# Prototipo_1_0.net
KiCad netlist of a schematic drawn in EAGLE
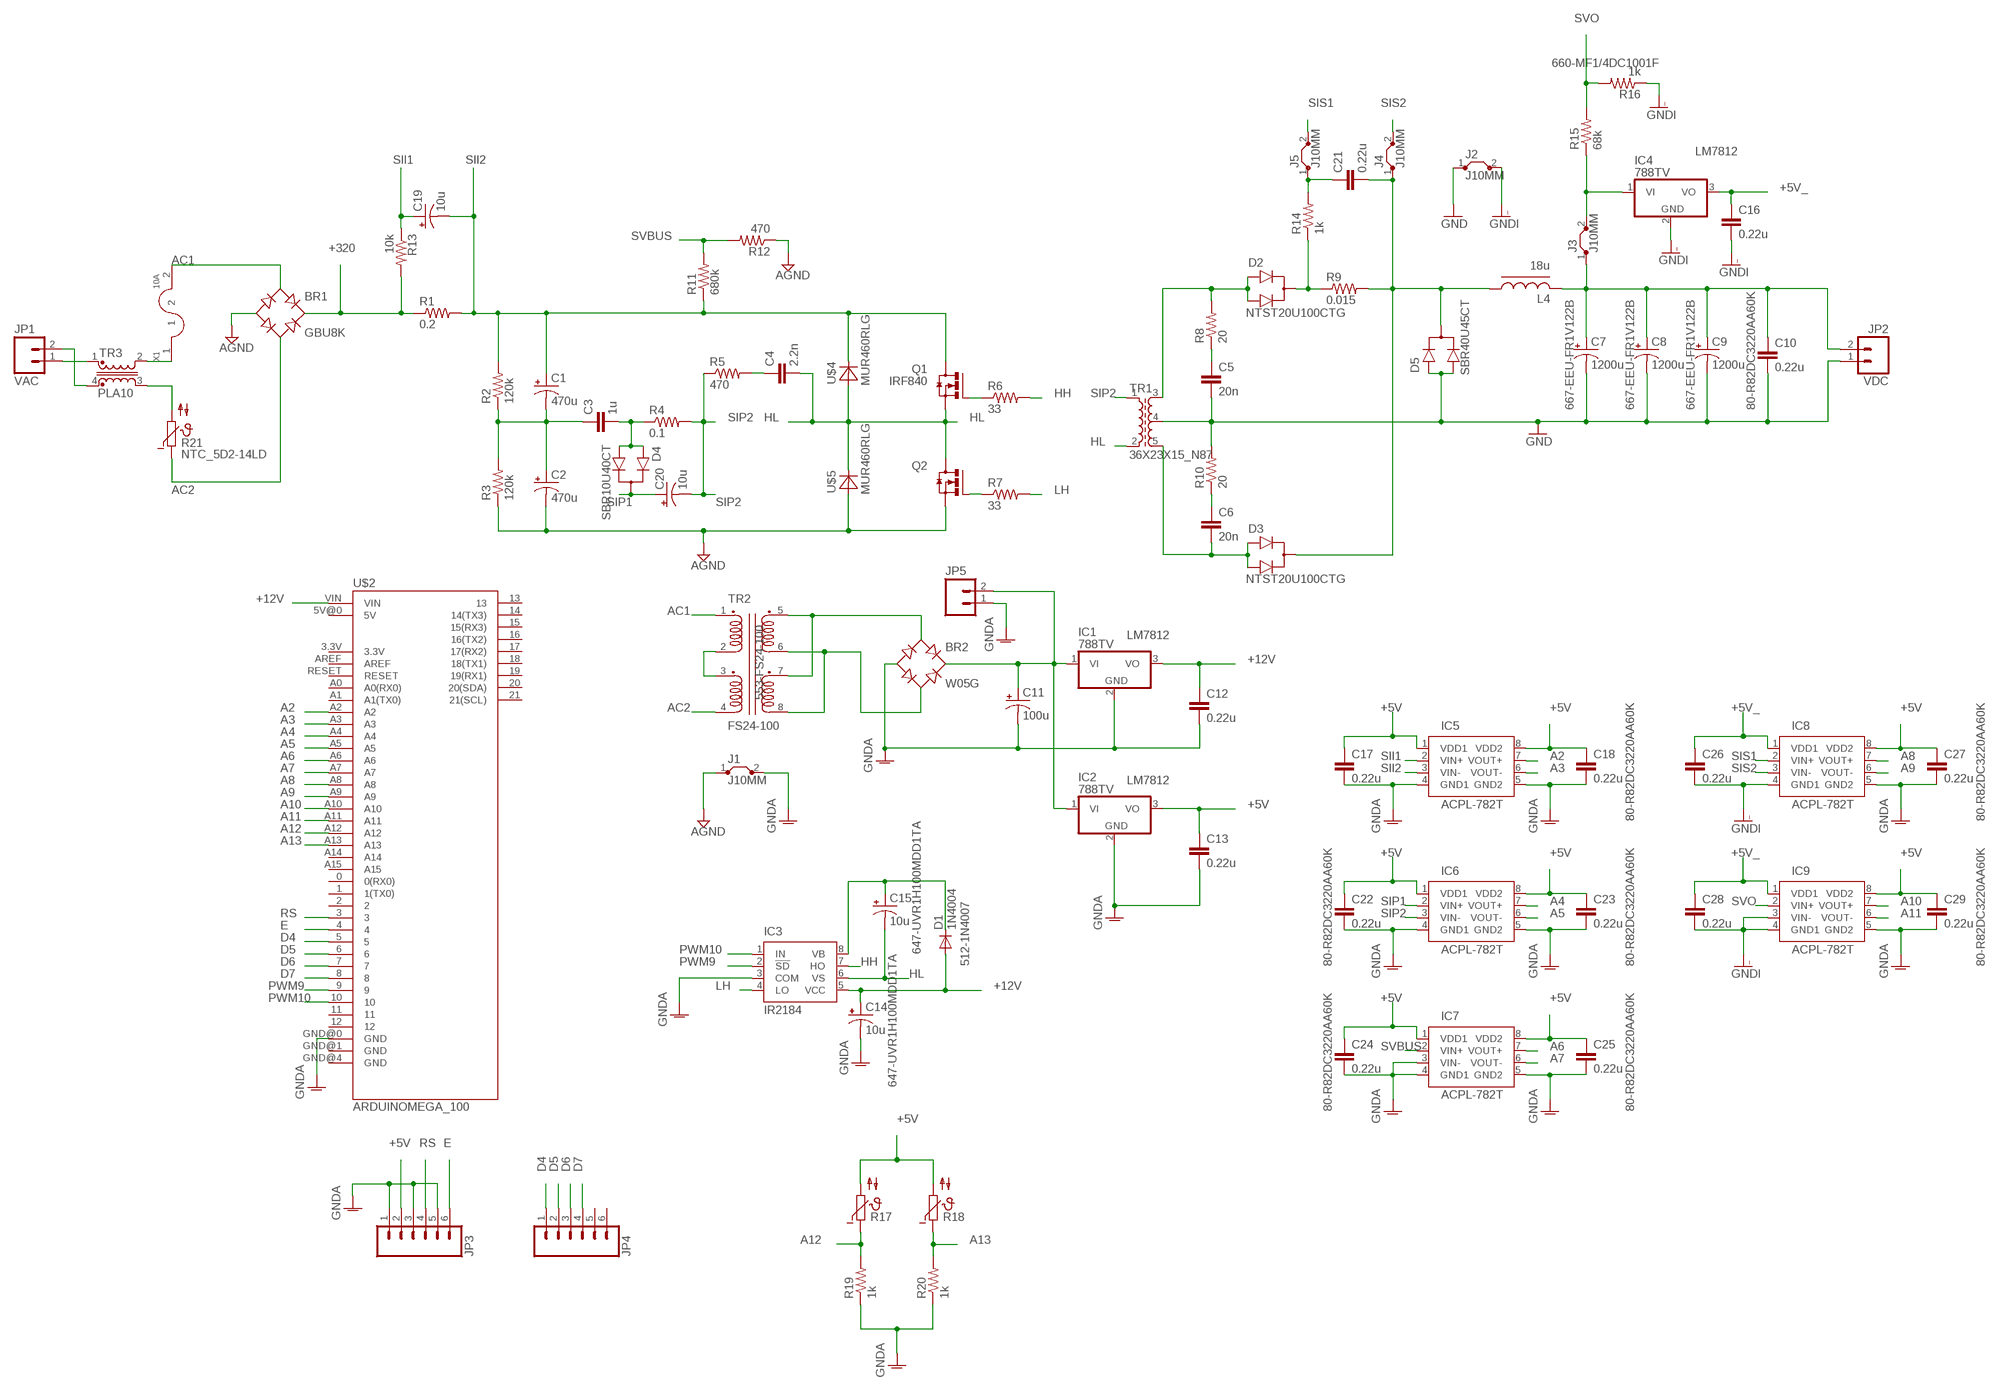
[diagram p0: schematic, sheet 1]

(export (version "E")
  (design (tool "Eeschema 10.0.6"))
  (components
    (comp (ref "BR1")
      (value "GBU8K")
      (footprint "eagle-import:GBU")
      (libsource (lib "eagle-import") (part "GBU8K"))
    )
    (comp (ref "BR2")
      (value "W05G")
      (footprint "eagle-import:WOG")
      (libsource (lib "eagle-import") (part "WG05"))
    )
    (comp (ref "C1")
      (value "470u")
      (footprint "eagle-import:CPOL_RADIAL_470UF_250V")
      (libsource (lib "eagle-import") (part "CAP_470UF_250V"))
    )
    (comp (ref "C2")
      (value "470u")
      (footprint "eagle-import:CPOL_RADIAL_470UF_250V")
      (libsource (lib "eagle-import") (part "CAP_470UF_250V"))
    )
    (comp (ref "C3")
      (value "1u")
      (footprint "eagle-import:C22.5B8")
      (libsource (lib "eagle-import") (part "C22/8"))
    )
    (comp (ref "C4")
      (value "2.2n")
      (footprint "eagle-import:C7.5B4")
      (libsource (lib "eagle-import") (part "C7.5/4"))
    )
    (comp (ref "C5")
      (value "20n")
      (footprint "eagle-import:C10B4")
      (libsource (lib "eagle-import") (part "C10/4"))
    )
    (comp (ref "C6")
      (value "20n")
      (footprint "eagle-import:C10B4")
      (libsource (lib "eagle-import") (part "C10/4"))
    )
    (comp (ref "C7")
      (value "1200u")
      (footprint "eagle-import:CPOL-RADIAL-1000UF-25V")
      (fields (field (name "MOUSER") "667-EEU-FR1V122B"))
      (libsource (lib "eagle-import") (part "CAP_POLPTH4"))
    )
    (comp (ref "C8")
      (value "1200u")
      (footprint "eagle-import:CPOL-RADIAL-1000UF-25V")
      (fields (field (name "MOUSER") "667-EEU-FR1V122B"))
      (libsource (lib "eagle-import") (part "CAP_POLPTH4"))
    )
    (comp (ref "C9")
      (value "1200u")
      (footprint "eagle-import:CPOL-RADIAL-1000UF-25V")
      (fields (field (name "MOUSER") "667-EEU-FR1V122B"))
      (libsource (lib "eagle-import") (part "CAP_POLPTH4"))
    )
    (comp (ref "C10")
      (value "0.22u")
      (footprint "eagle-import:C5B3")
      (fields (field (name "MOUSER") "80-R82DC3220AA60K "))
      (libsource (lib "eagle-import") (part "C5/3"))
    )
    (comp (ref "C11")
      (value "100u")
      (footprint "eagle-import:E3,5-8")
      (libsource (lib "eagle-import") (part "CPOL-USE3.5-8"))
    )
    (comp (ref "C12")
      (value "0.22u")
      (footprint "eagle-import:C5B3")
      (libsource (lib "eagle-import") (part "C5/3"))
    )
    (comp (ref "C13")
      (value "0.22u")
      (footprint "eagle-import:C5B3")
      (libsource (lib "eagle-import") (part "C5/3"))
    )
    (comp (ref "C14")
      (value "10u")
      (footprint "eagle-import:E2,5-6E")
      (fields (field (name "MOUSER") "647-UVR1H100MDD1TA"))
      (libsource (lib "eagle-import") (part "CPOL-USE2,5-6E"))
    )
    (comp (ref "C15")
      (value "10u")
      (footprint "eagle-import:E2,5-6E")
      (fields (field (name "MOUSER") "647-UVR1H100MDD1TA"))
      (libsource (lib "eagle-import") (part "CPOL-USE2,5-6E"))
    )
    (comp (ref "C16")
      (value "0.22u")
      (footprint "eagle-import:C5B3")
      (libsource (lib "eagle-import") (part "C5/3"))
    )
    (comp (ref "C17")
      (value "0.22u")
      (footprint "eagle-import:C5B3")
      (libsource (lib "eagle-import") (part "C5/3"))
    )
    (comp (ref "C18")
      (value "0.22u")
      (footprint "eagle-import:C5B3")
      (fields (field (name "MOUSER") "80-R82DC3220AA60K "))
      (libsource (lib "eagle-import") (part "C5/3"))
    )
    (comp (ref "C19")
      (value "10u")
      (footprint "eagle-import:E2,5-6E")
      (libsource (lib "eagle-import") (part "CPOL-USE2,5-6E"))
    )
    (comp (ref "C20")
      (value "10u")
      (footprint "eagle-import:E2,5-6E")
      (libsource (lib "eagle-import") (part "CPOL-USE2,5-6E"))
    )
    (comp (ref "C21")
      (value "0.22u")
      (footprint "eagle-import:C5B3")
      (libsource (lib "eagle-import") (part "C5/3"))
    )
    (comp (ref "C22")
      (value "0.22u")
      (footprint "eagle-import:C5B3")
      (fields (field (name "MOUSER") "80-R82DC3220AA60K "))
      (libsource (lib "eagle-import") (part "C5/3"))
    )
    (comp (ref "C23")
      (value "0.22u")
      (footprint "eagle-import:C5B3")
      (fields (field (name "MOUSER") "80-R82DC3220AA60K "))
      (libsource (lib "eagle-import") (part "C5/3"))
    )
    (comp (ref "C24")
      (value "0.22u")
      (footprint "eagle-import:C5B3")
      (fields (field (name "MOUSER") "80-R82DC3220AA60K "))
      (libsource (lib "eagle-import") (part "C5/3"))
    )
    (comp (ref "C25")
      (value "0.22u")
      (footprint "eagle-import:C5B3")
      (fields (field (name "MOUSER") "80-R82DC3220AA60K "))
      (libsource (lib "eagle-import") (part "C5/3"))
    )
    (comp (ref "C26")
      (value "0.22u")
      (footprint "eagle-import:C5B3")
      (libsource (lib "eagle-import") (part "C5/3"))
    )
    (comp (ref "C27")
      (value "0.22u")
      (footprint "eagle-import:C5B3")
      (fields (field (name "MOUSER") "80-R82DC3220AA60K "))
      (libsource (lib "eagle-import") (part "C5/3"))
    )
    (comp (ref "C28")
      (value "0.22u")
      (footprint "eagle-import:C5B3")
      (libsource (lib "eagle-import") (part "C5/3"))
    )
    (comp (ref "C29")
      (value "0.22u")
      (footprint "eagle-import:C5B3")
      (fields (field (name "MOUSER") "80-R82DC3220AA60K "))
      (libsource (lib "eagle-import") (part "C5/3"))
    )
    (comp (ref "D1")
      (value "1N4004")
      (footprint "eagle-import:DO41-10")
      (fields (field (name "MOUSER") "512-1N4007"))
      (libsource (lib "eagle-import") (part "1N4004"))
    )
    (comp (ref "D2")
      (value "NTST20U100CTG")
      (footprint "eagle-import:TO220V")
      (libsource (lib "eagle-import") (part "NTST20U100CTG"))
    )
    (comp (ref "D3")
      (value "NTST20U100CTG")
      (footprint "eagle-import:TO220V")
      (libsource (lib "eagle-import") (part "NTST20U100CTG"))
    )
    (comp (ref "D4")
      (value "SBR10U40CT")
      (footprint "eagle-import:TO220V")
      (libsource (lib "eagle-import") (part "SBR10U40CT"))
    )
    (comp (ref "D5")
      (value "SBR40U45CT")
      (footprint "eagle-import:TO220V")
      (libsource (lib "eagle-import") (part "SBR40U45CT"))
    )
    (comp (ref "IC1")
      (value "788TV")
      (footprint "eagle-import:TO220V")
      (fields (field (name "MODEL") "LM7812"))
      (libsource (lib "eagle-import") (part "78TV8"))
    )
    (comp (ref "IC2")
      (value "788TV")
      (footprint "eagle-import:TO220V")
      (fields (field (name "MODEL") "LM7812"))
      (libsource (lib "eagle-import") (part "78TV8"))
    )
    (comp (ref "IC3")
      (value "IR2184")
      (footprint "eagle-import:DIL08")
      (fields (field (name "MF") "INTERNATIONAL RECTIFIER(IR)"))
      (libsource (lib "eagle-import") (part "IR2184"))
    )
    (comp (ref "IC4")
      (value "788TV")
      (footprint "eagle-import:TO220V")
      (fields (field (name "MODEL") "LM7812"))
      (libsource (lib "eagle-import") (part "78TV8"))
    )
    (comp (ref "IC5")
      (value "ACPL-782T")
      (footprint "eagle-import:DIL08")
      (libsource (lib "eagle-import") (part "ACPL-782T"))
    )
    (comp (ref "IC6")
      (value "ACPL-782T")
      (footprint "eagle-import:DIL08")
      (libsource (lib "eagle-import") (part "ACPL-782T"))
    )
    (comp (ref "IC7")
      (value "ACPL-782T")
      (footprint "eagle-import:DIL08")
      (libsource (lib "eagle-import") (part "ACPL-782T"))
    )
    (comp (ref "IC8")
      (value "ACPL-782T")
      (footprint "eagle-import:DIL08")
      (libsource (lib "eagle-import") (part "ACPL-782T"))
    )
    (comp (ref "IC9")
      (value "ACPL-782T")
      (footprint "eagle-import:DIL08")
      (libsource (lib "eagle-import") (part "ACPL-782T"))
    )
    (comp (ref "J1")
      (value "J10MM")
      (footprint "eagle-import:10")
      (libsource (lib "eagle-import") (part "J10MM"))
    )
    (comp (ref "J2")
      (value "J10MM")
      (footprint "eagle-import:10")
      (libsource (lib "eagle-import") (part "J10MM"))
    )
    (comp (ref "J3")
      (value "J10MM")
      (footprint "eagle-import:10")
      (libsource (lib "eagle-import") (part "J10MM"))
    )
    (comp (ref "J4")
      (value "J10MM")
      (footprint "eagle-import:10")
      (libsource (lib "eagle-import") (part "J10MM"))
    )
    (comp (ref "J5")
      (value "J10MM")
      (footprint "eagle-import:10")
      (libsource (lib "eagle-import") (part "J10MM"))
    )
    (comp (ref "JP1")
      (value "VAC")
      (footprint "eagle-import:SCREWTERMINAL-3.5MM-2")
      (libsource (lib "eagle-import") (part "M023.5MM"))
    )
    (comp (ref "JP2")
      (value "VDC")
      (footprint "eagle-import:SCREWTERMINAL-5MM-2")
      (libsource (lib "eagle-import") (part "M025MM"))
    )
    (comp (ref "JP3")
      (value "M06SIP")
      (footprint "eagle-import:1X06")
      (libsource (lib "eagle-import") (part "M06SIP"))
    )
    (comp (ref "JP4")
      (value "M06SIP")
      (footprint "eagle-import:1X06")
      (libsource (lib "eagle-import") (part "M06SIP"))
    )
    (comp (ref "JP5")
      (value "M02LOCK_LONGPADS")
      (footprint "eagle-import:1X02_LOCK_LONGPADS")
      (libsource (lib "eagle-import") (part "M02LOCK_LONGPADS"))
    )
    (comp (ref "L4")
      (value "18u")
      (footprint "eagle-import:CHOKE_18U")
      (libsource (lib "eagle-import") (part "CHOKE_18U"))
    )
    (comp (ref "Q1")
      (value "IRF840")
      (footprint "eagle-import:TO220HV")
      (libsource (lib "eagle-import") (part "IRF840"))
    )
    (comp (ref "Q2")
      (value "IRF840")
      (footprint "eagle-import:TO220HV")
      (libsource (lib "eagle-import") (part "IRF840"))
    )
    (comp (ref "R1")
      (value "0.2")
      (footprint "eagle-import:AXIAL-0.6")
      (libsource (lib "eagle-import") (part "RESISTORPTH-1W"))
    )
    (comp (ref "R2")
      (value "120k")
      (footprint "eagle-import:AXIAL-0.4")
      (libsource (lib "eagle-import") (part "RESISTORPTH-1/4W"))
    )
    (comp (ref "R3")
      (value "120k")
      (footprint "eagle-import:AXIAL-0.4")
      (libsource (lib "eagle-import") (part "RESISTORPTH-1/4W"))
    )
    (comp (ref "R4")
      (value "0.1")
      (footprint "eagle-import:RESISTOR_2W")
      (libsource (lib "eagle-import") (part "RESISTOR_2W"))
    )
    (comp (ref "R5")
      (value "470")
      (footprint "eagle-import:0922V")
      (libsource (lib "eagle-import") (part "R-US_0922V"))
    )
    (comp (ref "R6")
      (value "33")
      (footprint "eagle-import:AXIAL-0.5")
      (libsource (lib "eagle-import") (part "RESISTORPTH-1/2W"))
    )
    (comp (ref "R7")
      (value "33")
      (footprint "eagle-import:AXIAL-0.5")
      (libsource (lib "eagle-import") (part "RESISTORPTH-1/2W"))
    )
    (comp (ref "R8")
      (value "20")
      (footprint "eagle-import:AXIAL-0.5")
      (libsource (lib "eagle-import") (part "RESISTORPTH-1/2W"))
    )
    (comp (ref "R9")
      (value "0.015")
      (footprint "eagle-import:RSENSE")
      (libsource (lib "eagle-import") (part "RSENSE"))
    )
    (comp (ref "R10")
      (value "20")
      (footprint "eagle-import:AXIAL-0.5")
      (libsource (lib "eagle-import") (part "RESISTORPTH-1/2W"))
    )
    (comp (ref "R11")
      (value "680k")
      (footprint "eagle-import:AXIAL-0.4")
      (libsource (lib "eagle-import") (part "RESISTORPTH-1/4W"))
    )
    (comp (ref "R12")
      (value "470")
      (footprint "eagle-import:AXIAL-0.4")
      (libsource (lib "eagle-import") (part "RESISTORPTH-1/4W"))
    )
    (comp (ref "R13")
      (value "10k")
      (footprint "eagle-import:AXIAL-0.4")
      (libsource (lib "eagle-import") (part "RESISTORPTH-1/4W"))
    )
    (comp (ref "R14")
      (value "1k")
      (footprint "eagle-import:AXIAL-0.4")
      (libsource (lib "eagle-import") (part "RESISTORPTH-1/4W"))
    )
    (comp (ref "R15")
      (value "68k")
      (footprint "eagle-import:AXIAL-0.4")
      (libsource (lib "eagle-import") (part "RESISTORPTH-1/4W"))
    )
    (comp (ref "R16")
      (value "1k")
      (footprint "eagle-import:AXIAL-0.4")
      (fields (field (name "MOUSER") "660-MF1/4DC1001F"))
      (libsource (lib "eagle-import") (part "RESISTORPTH-1/4W"))
    )
    (comp (ref "R17")
      (value "NTC640")
      (footprint "eagle-import:P640")
      (libsource (lib "eagle-import") (part "NTC640"))
    )
    (comp (ref "R18")
      (value "NTC640")
      (footprint "eagle-import:P640")
      (fields (field (name "OC_FARNELL") "unknown") (field (name "OC_NEWARK") "unknown"))
      (libsource (lib "eagle-import") (part "NTC640"))
    )
    (comp (ref "R19")
      (value "1k")
      (footprint "eagle-import:AXIAL-0.4")
      (libsource (lib "eagle-import") (part "RESISTORPTH-1/4W"))
    )
    (comp (ref "R20")
      (value "1k")
      (footprint "eagle-import:AXIAL-0.4")
      (libsource (lib "eagle-import") (part "RESISTORPTH-1/4W"))
    )
    (comp (ref "R21")
      (value "NTC_5D2-14LD")
      (footprint "eagle-import:C075-042X103")
      (libsource (lib "eagle-import") (part "NTC_5D2-14LD"))
    )
    (comp (ref "TR1")
      (value "36X23X15_N87")
      (footprint "eagle-import:CORE_36X23X15")
      (libsource (lib "eagle-import") (part "36X23X15_N87"))
    )
    (comp (ref "TR2")
      (value "FS24-100")
      (footprint "eagle-import:FS24-100")
      (fields (field (name "MOUSER") "553-FS24-100"))
      (libsource (lib "eagle-import") (part "FS24-100"))
    )
    (comp (ref "TR3")
      (value "PLA10")
      (footprint "eagle-import:COMMON_MODE_CHOKE_PLA10")
      (libsource (lib "eagle-import") (part "COMMON_MODE_CHOKE_PLA10"))
    )
    (comp (ref "U$2")
      (value "ARDUINOMEGA_100")
      (footprint "eagle-import:ARDUINOMEGA_100")
      (libsource (lib "eagle-import") (part "ARDUINOMEGA_100"))
    )
    (comp (ref "U$4")
      (value "MUR460RLG")
      (footprint "eagle-import:CB429-17")
      (libsource (lib "eagle-import") (part "MUR460RLG"))
    )
    (comp (ref "U$5")
      (value "MUR460RLG")
      (footprint "eagle-import:CB429-17")
      (libsource (lib "eagle-import") (part "MUR460RLG"))
    )
    (comp (ref "X1")
      (value "10A")
      (footprint "eagle-import:FUSE_HOLDER_5X20")
      (libsource (lib "eagle-import") (part "FUSE_HOLDER_5X20"))
    )
  )
  (nets
    (net (code "1") (name "/+5V") (class "Default")
      (node (ref "C13") (pin "1") (pinfunction "1_1") (pintype "passive"))
      (node (ref "C17") (pin "1") (pinfunction "1_1") (pintype "passive"))
      (node (ref "C18") (pin "1") (pinfunction "1_1") (pintype "passive"))
      (node (ref "C22") (pin "1") (pinfunction "1_1") (pintype "passive"))
      (node (ref "C23") (pin "1") (pinfunction "1_1") (pintype "passive"))
      (node (ref "C24") (pin "1") (pinfunction "1_1") (pintype "passive"))
      (node (ref "C25") (pin "1") (pinfunction "1_1") (pintype "passive"))
      (node (ref "C27") (pin "1") (pinfunction "1_1") (pintype "passive"))
      (node (ref "C29") (pin "1") (pinfunction "1_1") (pintype "passive"))
      (node (ref "IC2") (pin "3") (pinfunction "VO_3") (pintype "passive"))
      (node (ref "IC5") (pin "1") (pinfunction "VDD1_1") (pintype "power_in"))
      (node (ref "IC5") (pin "8") (pinfunction "VDD2_8") (pintype "power_in"))
      (node (ref "IC6") (pin "1") (pinfunction "VDD1_1") (pintype "power_in"))
      (node (ref "IC6") (pin "8") (pinfunction "VDD2_8") (pintype "power_in"))
      (node (ref "IC7") (pin "1") (pinfunction "VDD1_1") (pintype "power_in"))
      (node (ref "IC7") (pin "8") (pinfunction "VDD2_8") (pintype "power_in"))
      (node (ref "IC8") (pin "8") (pinfunction "VDD2_8") (pintype "power_in"))
      (node (ref "IC9") (pin "8") (pinfunction "VDD2_8") (pintype "power_in"))
      (node (ref "JP3") (pin "2") (pinfunction "2_2") (pintype "passive"))
      (node (ref "R17") (pin "2") (pinfunction "2_2") (pintype "passive"))
      (node (ref "R18") (pin "2") (pinfunction "2_2") (pintype "passive"))
    )
    (net (code "2") (name "/+5V_") (class "Default")
      (node (ref "C16") (pin "1") (pinfunction "1_1") (pintype "passive"))
      (node (ref "C26") (pin "1") (pinfunction "1_1") (pintype "passive"))
      (node (ref "C28") (pin "1") (pinfunction "1_1") (pintype "passive"))
      (node (ref "IC4") (pin "3") (pinfunction "VO_3") (pintype "passive"))
      (node (ref "IC8") (pin "1") (pinfunction "VDD1_1") (pintype "power_in"))
      (node (ref "IC9") (pin "1") (pinfunction "VDD1_1") (pintype "power_in"))
    )
    (net (code "3") (name "/+12V") (class "Default")
      (node (ref "C12") (pin "1") (pinfunction "1_1") (pintype "passive"))
      (node (ref "C14") (pin "+") (pinfunction "+_+") (pintype "passive"))
      (node (ref "D1") (pin "A") (pinfunction "A_A") (pintype "passive"))
      (node (ref "IC1") (pin "3") (pinfunction "VO_3") (pintype "passive"))
      (node (ref "IC3") (pin "5") (pinfunction "VCC_5") (pintype "output"))
      (node (ref "U$2") (pin "VIN") (pinfunction "VIN_VIN") (pintype "bidirectional"))
    )
    (net (code "4") (name "/+320") (class "Default")
      (node (ref "BR1") (pin "4") (pinfunction "+_4") (pintype "passive"))
      (node (ref "R1") (pin "P$1") (pinfunction "1_P$1") (pintype "passive"))
      (node (ref "R13") (pin "P$2") (pinfunction "2_P$2") (pintype "passive"))
    )
    (net (code "5") (name "/A2") (class "Default")
      (node (ref "IC5") (pin "7") (pinfunction "VOUT+_7") (pintype "output"))
      (node (ref "U$2") (pin "A2") (pinfunction "A2_A2") (pintype "bidirectional"))
    )
    (net (code "6") (name "/A3") (class "Default")
      (node (ref "IC5") (pin "6") (pinfunction "VOUT-_6") (pintype "output"))
      (node (ref "U$2") (pin "A3") (pinfunction "A3_A3") (pintype "bidirectional"))
    )
    (net (code "7") (name "/A4") (class "Default")
      (node (ref "IC6") (pin "7") (pinfunction "VOUT+_7") (pintype "output"))
      (node (ref "U$2") (pin "A4") (pinfunction "A4_A4") (pintype "bidirectional"))
    )
    (net (code "8") (name "/A5") (class "Default")
      (node (ref "IC6") (pin "6") (pinfunction "VOUT-_6") (pintype "output"))
      (node (ref "U$2") (pin "A5") (pinfunction "A5_A5") (pintype "bidirectional"))
    )
    (net (code "9") (name "/A6") (class "Default")
      (node (ref "IC7") (pin "7") (pinfunction "VOUT+_7") (pintype "output"))
      (node (ref "U$2") (pin "A6") (pinfunction "A6_A6") (pintype "bidirectional"))
    )
    (net (code "10") (name "/A7") (class "Default")
      (node (ref "IC7") (pin "6") (pinfunction "VOUT-_6") (pintype "output"))
      (node (ref "U$2") (pin "A7") (pinfunction "A7_A7") (pintype "bidirectional"))
    )
    (net (code "11") (name "/A8") (class "Default")
      (node (ref "IC8") (pin "7") (pinfunction "VOUT+_7") (pintype "output"))
      (node (ref "U$2") (pin "A8") (pinfunction "A8_A8") (pintype "bidirectional"))
    )
    (net (code "12") (name "/A9") (class "Default")
      (node (ref "IC8") (pin "6") (pinfunction "VOUT-_6") (pintype "output"))
      (node (ref "U$2") (pin "A9") (pinfunction "A9_A9") (pintype "bidirectional"))
    )
    (net (code "13") (name "/A10") (class "Default")
      (node (ref "IC9") (pin "7") (pinfunction "VOUT+_7") (pintype "output"))
      (node (ref "U$2") (pin "A10") (pinfunction "A10_A10") (pintype "bidirectional"))
    )
    (net (code "14") (name "/A11") (class "Default")
      (node (ref "IC9") (pin "6") (pinfunction "VOUT-_6") (pintype "output"))
      (node (ref "U$2") (pin "A11") (pinfunction "A11_A11") (pintype "bidirectional"))
    )
    (net (code "15") (name "/A12") (class "Default")
      (node (ref "R17") (pin "1") (pinfunction "1_1") (pintype "passive"))
      (node (ref "R19") (pin "P$2") (pinfunction "2_P$2") (pintype "passive"))
      (node (ref "U$2") (pin "A12") (pinfunction "A12_A12") (pintype "bidirectional"))
    )
    (net (code "16") (name "/A13") (class "Default")
      (node (ref "R18") (pin "1") (pinfunction "1_1") (pintype "passive"))
      (node (ref "R20") (pin "P$2") (pinfunction "2_P$2") (pintype "passive"))
      (node (ref "U$2") (pin "A13") (pinfunction "A13_A13") (pintype "bidirectional"))
    )
    (net (code "17") (name "/AC1") (class "Default")
      (node (ref "BR1") (pin "2") (pinfunction "AC1_2") (pintype "passive"))
      (node (ref "TR2") (pin "1") (pinfunction "P1.1_1") (pintype "passive"))
      (node (ref "X1") (pin "2") (pinfunction "2_2") (pintype "bidirectional"))
    )
    (net (code "18") (name "/AC2") (class "Default")
      (node (ref "BR1") (pin "3") (pinfunction "AC2_3") (pintype "passive"))
      (node (ref "R21") (pin "1") (pinfunction "1_1") (pintype "passive"))
      (node (ref "TR2") (pin "4") (pinfunction "P2.2_4") (pintype "passive"))
    )
    (net (code "19") (name "/D4") (class "Default")
      (node (ref "JP4") (pin "1") (pinfunction "1_1") (pintype "passive"))
      (node (ref "U$2") (pin "5") (pinfunction "5_5") (pintype "bidirectional"))
    )
    (net (code "20") (name "/D5") (class "Default")
      (node (ref "JP4") (pin "2") (pinfunction "2_2") (pintype "passive"))
      (node (ref "U$2") (pin "6") (pinfunction "6_6") (pintype "bidirectional"))
    )
    (net (code "21") (name "/D6") (class "Default")
      (node (ref "JP4") (pin "3") (pinfunction "3_3") (pintype "passive"))
      (node (ref "U$2") (pin "7") (pinfunction "7_7") (pintype "bidirectional"))
    )
    (net (code "22") (name "/D7") (class "Default")
      (node (ref "JP4") (pin "4") (pinfunction "4_4") (pintype "passive"))
      (node (ref "U$2") (pin "8") (pinfunction "8_8") (pintype "bidirectional"))
    )
    (net (code "23") (name "/E") (class "Default")
      (node (ref "JP3") (pin "6") (pinfunction "6_6") (pintype "passive"))
      (node (ref "U$2") (pin "4") (pinfunction "4_4") (pintype "bidirectional"))
    )
    (net (code "24") (name "/HH") (class "Default")
      (node (ref "IC3") (pin "7") (pinfunction "HO_7") (pintype "passive"))
      (node (ref "R6") (pin "P$2") (pinfunction "2_P$2") (pintype "passive"))
    )
    (net (code "25") (name "/HL") (class "Default")
      (node (ref "C15") (pin "-") (pinfunction "-_-") (pintype "passive"))
      (node (ref "C4") (pin "2") (pinfunction "2_2") (pintype "passive"))
      (node (ref "IC3") (pin "6") (pinfunction "VS_6") (pintype "input"))
      (node (ref "Q1") (pin "3") (pinfunction "S_3") (pintype "passive"))
      (node (ref "Q2") (pin "2") (pinfunction "D_2") (pintype "passive"))
      (node (ref "TR1") (pin "2") (pinfunction "2_2") (pintype "passive"))
      (node (ref "U$4") (pin "A") (pinfunction "A_A") (pintype "passive"))
      (node (ref "U$5") (pin "C") (pinfunction "C_C") (pintype "passive"))
    )
    (net (code "26") (name "/LH") (class "Default")
      (node (ref "IC3") (pin "4") (pinfunction "LO_4") (pintype "power_in"))
      (node (ref "R7") (pin "P$2") (pinfunction "2_P$2") (pintype "passive"))
    )
    (net (code "27") (name "/PWM9") (class "Default")
      (node (ref "IC3") (pin "2") (pinfunction "~{SD}_2") (pintype "input"))
      (node (ref "U$2") (pin "9") (pinfunction "9_9") (pintype "bidirectional"))
    )
    (net (code "28") (name "/PWM10") (class "Default")
      (node (ref "IC3") (pin "1") (pinfunction "IN_1") (pintype "power_in"))
      (node (ref "U$2") (pin "10") (pinfunction "10_10") (pintype "bidirectional"))
    )
    (net (code "29") (name "/RS") (class "Default")
      (node (ref "JP3") (pin "4") (pinfunction "4_4") (pintype "passive"))
      (node (ref "U$2") (pin "3") (pinfunction "3_3") (pintype "bidirectional"))
    )
    (net (code "30") (name "/SII1") (class "Default")
      (node (ref "C19") (pin "+") (pinfunction "+_+") (pintype "passive"))
      (node (ref "IC5") (pin "2") (pinfunction "VIN+_2") (pintype "input"))
      (node (ref "R13") (pin "P$1") (pinfunction "1_P$1") (pintype "passive"))
    )
    (net (code "31") (name "/SII2") (class "Default")
      (node (ref "C1") (pin "1") (pinfunction "+_1") (pintype "passive"))
      (node (ref "C19") (pin "-") (pinfunction "-_-") (pintype "passive"))
      (node (ref "IC5") (pin "3") (pinfunction "VIN-_3") (pintype "input"))
      (node (ref "Q1") (pin "2") (pinfunction "D_2") (pintype "passive"))
      (node (ref "R1") (pin "P$2") (pinfunction "2_P$2") (pintype "passive"))
      (node (ref "R11") (pin "P$1") (pinfunction "1_P$1") (pintype "passive"))
      (node (ref "R2") (pin "P$2") (pinfunction "2_P$2") (pintype "passive"))
      (node (ref "U$4") (pin "C") (pinfunction "C_C") (pintype "passive"))
    )
    (net (code "32") (name "/SIP1") (class "Default")
      (node (ref "C20") (pin "+") (pinfunction "+_+") (pintype "passive"))
      (node (ref "D4") (pin "2") (pinfunction "C_2") (pintype "passive"))
      (node (ref "IC6") (pin "2") (pinfunction "VIN+_2") (pintype "input"))
    )
    (net (code "33") (name "/SIP2") (class "Default")
      (node (ref "C20") (pin "-") (pinfunction "-_-") (pintype "passive"))
      (node (ref "IC6") (pin "3") (pinfunction "VIN-_3") (pintype "input"))
      (node (ref "R4") (pin "2") (pinfunction "2_2") (pintype "passive"))
      (node (ref "R5") (pin "1") (pinfunction "1_1") (pintype "passive"))
      (node (ref "TR1") (pin "1") (pinfunction "1_1") (pintype "passive"))
    )
    (net (code "34") (name "/SIS1") (class "Default")
      (node (ref "IC8") (pin "2") (pinfunction "VIN+_2") (pintype "input"))
      (node (ref "J5") (pin "2") (pinfunction "2_2") (pintype "passive"))
    )
    (net (code "35") (name "/SIS2") (class "Default")
      (node (ref "IC8") (pin "3") (pinfunction "VIN-_3") (pintype "input"))
      (node (ref "J4") (pin "2") (pinfunction "2_2") (pintype "passive"))
    )
    (net (code "36") (name "/SVBUS") (class "Default")
      (node (ref "IC7") (pin "2") (pinfunction "VIN+_2") (pintype "input"))
      (node (ref "R11") (pin "P$2") (pinfunction "2_P$2") (pintype "passive"))
      (node (ref "R12") (pin "P$2") (pinfunction "2_P$2") (pintype "passive"))
    )
    (net (code "37") (name "/SVO") (class "Default")
      (node (ref "IC9") (pin "2") (pinfunction "VIN+_2") (pintype "input"))
      (node (ref "R15") (pin "P$2") (pinfunction "2_P$2") (pintype "passive"))
      (node (ref "R16") (pin "P$2") (pinfunction "2_P$2") (pintype "passive"))
    )
    (net (code "38") (name "AGND") (class "Default")
      (node (ref "BR1") (pin "1") (pinfunction "-_1") (pintype "passive"))
      (node (ref "C2") (pin "2") (pinfunction "-_2") (pintype "passive"))
      (node (ref "J1") (pin "1") (pinfunction "1_1") (pintype "passive"))
      (node (ref "Q2") (pin "3") (pinfunction "S_3") (pintype "passive"))
      (node (ref "R12") (pin "P$1") (pinfunction "1_P$1") (pintype "passive"))
      (node (ref "R3") (pin "P$1") (pinfunction "1_P$1") (pintype "passive"))
      (node (ref "U$5") (pin "A") (pinfunction "A_A") (pintype "passive"))
    )
    (net (code "39") (name "GND") (class "Default")
      (node (ref "C10") (pin "2") (pinfunction "2_2") (pintype "passive"))
      (node (ref "C5") (pin "2") (pinfunction "2_2") (pintype "passive"))
      (node (ref "C7") (pin "2") (pinfunction "-_2") (pintype "passive"))
      (node (ref "C8") (pin "2") (pinfunction "-_2") (pintype "passive"))
      (node (ref "C9") (pin "2") (pinfunction "-_2") (pintype "passive"))
      (node (ref "D5") (pin "1") (pinfunction "A1_1") (pintype "passive"))
      (node (ref "D5") (pin "3") (pinfunction "A2_3") (pintype "passive"))
      (node (ref "J2") (pin "1") (pinfunction "1_1") (pintype "passive"))
      (node (ref "JP2") (pin "1") (pinfunction "1_1") (pintype "passive"))
      (node (ref "R10") (pin "P$2") (pinfunction "2_P$2") (pintype "passive"))
      (node (ref "TR1") (pin "4") (pinfunction "4_4") (pintype "passive"))
    )
    (net (code "40") (name "GNDA") (class "Default")
      (node (ref "BR2") (pin "-") (pinfunction "-_-") (pintype "passive"))
      (node (ref "C11") (pin "-") (pinfunction "-_-") (pintype "passive"))
      (node (ref "C12") (pin "2") (pinfunction "2_2") (pintype "passive"))
      (node (ref "C13") (pin "2") (pinfunction "2_2") (pintype "passive"))
      (node (ref "C14") (pin "-") (pinfunction "-_-") (pintype "passive"))
      (node (ref "C17") (pin "2") (pinfunction "2_2") (pintype "passive"))
      (node (ref "C18") (pin "2") (pinfunction "2_2") (pintype "passive"))
      (node (ref "C22") (pin "2") (pinfunction "2_2") (pintype "passive"))
      (node (ref "C23") (pin "2") (pinfunction "2_2") (pintype "passive"))
      (node (ref "C24") (pin "2") (pinfunction "2_2") (pintype "passive"))
      (node (ref "C25") (pin "2") (pinfunction "2_2") (pintype "passive"))
      (node (ref "C27") (pin "2") (pinfunction "2_2") (pintype "passive"))
      (node (ref "C29") (pin "2") (pinfunction "2_2") (pintype "passive"))
      (node (ref "IC1") (pin "2") (pinfunction "GND_2") (pintype "passive"))
      (node (ref "IC2") (pin "2") (pinfunction "GND_2") (pintype "passive"))
      (node (ref "IC3") (pin "3") (pinfunction "COM_3") (pintype "input"))
      (node (ref "IC5") (pin "4") (pinfunction "GND1_4") (pintype "power_in"))
      (node (ref "IC5") (pin "5") (pinfunction "GND2_5") (pintype "power_in"))
      (node (ref "IC6") (pin "4") (pinfunction "GND1_4") (pintype "power_in"))
      (node (ref "IC6") (pin "5") (pinfunction "GND2_5") (pintype "power_in"))
      (node (ref "IC7") (pin "3") (pinfunction "VIN-_3") (pintype "input"))
      (node (ref "IC7") (pin "4") (pinfunction "GND1_4") (pintype "power_in"))
      (node (ref "IC7") (pin "5") (pinfunction "GND2_5") (pintype "power_in"))
      (node (ref "IC8") (pin "5") (pinfunction "GND2_5") (pintype "power_in"))
      (node (ref "IC9") (pin "5") (pinfunction "GND2_5") (pintype "power_in"))
      (node (ref "J1") (pin "2") (pinfunction "2_2") (pintype "passive"))
      (node (ref "JP3") (pin "1") (pinfunction "1_1") (pintype "passive"))
      (node (ref "JP3") (pin "3") (pinfunction "3_3") (pintype "passive"))
      (node (ref "JP3") (pin "5") (pinfunction "5_5") (pintype "passive"))
      (node (ref "JP5") (pin "1") (pinfunction "1_1") (pintype "passive"))
      (node (ref "R19") (pin "P$1") (pinfunction "1_P$1") (pintype "passive"))
      (node (ref "R20") (pin "P$1") (pinfunction "1_P$1") (pintype "passive"))
      (node (ref "U$2") (pin "GND@0") (pinfunction "GND_GND@0") (pintype "bidirectional"))
    )
    (net (code "41") (name "GNDI") (class "Default")
      (node (ref "C16") (pin "2") (pinfunction "2_2") (pintype "passive"))
      (node (ref "C26") (pin "2") (pinfunction "2_2") (pintype "passive"))
      (node (ref "C28") (pin "2") (pinfunction "2_2") (pintype "passive"))
      (node (ref "IC4") (pin "2") (pinfunction "GND_2") (pintype "passive"))
      (node (ref "IC8") (pin "4") (pinfunction "GND1_4") (pintype "power_in"))
      (node (ref "IC9") (pin "3") (pinfunction "VIN-_3") (pintype "input"))
      (node (ref "IC9") (pin "4") (pinfunction "GND1_4") (pintype "power_in"))
      (node (ref "J2") (pin "2") (pinfunction "2_2") (pintype "passive"))
      (node (ref "R16") (pin "P$1") (pinfunction "1_P$1") (pintype "passive"))
    )
    (net (code "42") (name "Net-(C1--)") (class "Default")
      (node (ref "C1") (pin "2") (pinfunction "-_2") (pintype "passive"))
      (node (ref "C2") (pin "1") (pinfunction "+_1") (pintype "passive"))
      (node (ref "C3") (pin "1") (pinfunction "1_1") (pintype "passive"))
      (node (ref "R2") (pin "P$1") (pinfunction "1_P$1") (pintype "passive"))
      (node (ref "R3") (pin "P$2") (pinfunction "2_P$2") (pintype "passive"))
    )
    (net (code "43") (name "Net-(C4-Pad1)") (class "Default")
      (node (ref "C4") (pin "1") (pinfunction "1_1") (pintype "passive"))
      (node (ref "R5") (pin "2") (pinfunction "2_2") (pintype "passive"))
    )
    (net (code "44") (name "Net-(C7-+)") (class "Default")
      (node (ref "C10") (pin "1") (pinfunction "1_1") (pintype "passive"))
      (node (ref "C7") (pin "1") (pinfunction "+_1") (pintype "passive"))
      (node (ref "C8") (pin "1") (pinfunction "+_1") (pintype "passive"))
      (node (ref "C9") (pin "1") (pinfunction "+_1") (pintype "passive"))
      (node (ref "J3") (pin "1") (pinfunction "1_1") (pintype "passive"))
      (node (ref "JP2") (pin "2") (pinfunction "2_2") (pintype "passive"))
      (node (ref "L4") (pin "2") (pinfunction "2_2") (pintype "passive"))
    )
    (net (code "45") (name "Net-(D2-A1)") (class "Default")
      (node (ref "D2") (pin "1") (pinfunction "A1_1") (pintype "passive"))
      (node (ref "D2") (pin "3") (pinfunction "A2_3") (pintype "passive"))
      (node (ref "R8") (pin "P$2") (pinfunction "2_P$2") (pintype "passive"))
      (node (ref "TR1") (pin "3") (pinfunction "3_3") (pintype "passive"))
    )
    (net (code "46") (name "Net-(D2-C)") (class "Default")
      (node (ref "D2") (pin "2") (pinfunction "C_2") (pintype "passive"))
      (node (ref "R14") (pin "P$1") (pinfunction "1_P$1") (pintype "passive"))
      (node (ref "R9") (pin "P$1") (pinfunction "1_P$1") (pintype "passive"))
    )
    (net (code "47") (name "Net-(D3-A1)") (class "Default")
      (node (ref "C6") (pin "2") (pinfunction "2_2") (pintype "passive"))
      (node (ref "D3") (pin "1") (pinfunction "A1_1") (pintype "passive"))
      (node (ref "D3") (pin "3") (pinfunction "A2_3") (pintype "passive"))
      (node (ref "TR1") (pin "5") (pinfunction "5_5") (pintype "passive"))
    )
    (net (code "48") (name "Net-(D3-C)") (class "Default")
      (node (ref "C21") (pin "2") (pinfunction "2_2") (pintype "passive"))
      (node (ref "D3") (pin "2") (pinfunction "C_2") (pintype "passive"))
      (node (ref "D5") (pin "2") (pinfunction "C_2") (pintype "passive"))
      (node (ref "J4") (pin "1") (pinfunction "1_1") (pintype "passive"))
      (node (ref "L4") (pin "1") (pinfunction "1_1") (pintype "passive"))
      (node (ref "R9") (pin "P$2") (pinfunction "2_P$2") (pintype "passive"))
    )
    (net (code "49") (name "Net-(D4-A1)") (class "Default")
      (node (ref "C3") (pin "2") (pinfunction "2_2") (pintype "passive"))
      (node (ref "D4") (pin "1") (pinfunction "A1_1") (pintype "passive"))
      (node (ref "D4") (pin "3") (pinfunction "A2_3") (pintype "passive"))
      (node (ref "R4") (pin "1") (pinfunction "1_1") (pintype "passive"))
    )
    (net (code "50") (name "Net-(IC1-VI)") (class "Default")
      (node (ref "BR2") (pin "+") (pinfunction "+_+") (pintype "passive"))
      (node (ref "C11") (pin "+") (pinfunction "+_+") (pintype "passive"))
      (node (ref "IC1") (pin "1") (pinfunction "VI_1") (pintype "input"))
      (node (ref "IC2") (pin "1") (pinfunction "VI_1") (pintype "input"))
      (node (ref "JP5") (pin "2") (pinfunction "2_2") (pintype "passive"))
    )
    (net (code "51") (name "Net-(IC3-VB)") (class "Default")
      (node (ref "C15") (pin "+") (pinfunction "+_+") (pintype "passive"))
      (node (ref "D1") (pin "C") (pinfunction "C_C") (pintype "passive"))
      (node (ref "IC3") (pin "8") (pinfunction "VB_8") (pintype "output"))
    )
    (net (code "52") (name "Net-(IC4-VI)") (class "Default")
      (node (ref "IC4") (pin "1") (pinfunction "VI_1") (pintype "input"))
      (node (ref "J3") (pin "2") (pinfunction "2_2") (pintype "passive"))
      (node (ref "R15") (pin "P$1") (pinfunction "1_P$1") (pintype "passive"))
    )
    (net (code "53") (name "Net-(JP1-Pad1)") (class "Default")
      (node (ref "JP1") (pin "1") (pinfunction "1_1") (pintype "passive"))
      (node (ref "TR3") (pin "1") (pinfunction "1_1") (pintype "passive"))
    )
    (net (code "54") (name "Net-(JP1-Pad2)") (class "Default")
      (node (ref "JP1") (pin "2") (pinfunction "2_2") (pintype "passive"))
      (node (ref "TR3") (pin "4") (pinfunction "4_4") (pintype "passive"))
    )
    (net (code "55") (name "Net-(Q1-G)") (class "Default")
      (node (ref "Q1") (pin "1") (pinfunction "G_1") (pintype "passive"))
      (node (ref "R6") (pin "P$1") (pinfunction "1_P$1") (pintype "passive"))
    )
    (net (code "56") (name "Net-(Q2-G)") (class "Default")
      (node (ref "Q2") (pin "1") (pinfunction "G_1") (pintype "passive"))
      (node (ref "R7") (pin "P$1") (pinfunction "1_P$1") (pintype "passive"))
    )
    (net (code "57") (name "Net-(R8-1)") (class "Default")
      (node (ref "C5") (pin "1") (pinfunction "1_1") (pintype "passive"))
      (node (ref "R8") (pin "P$1") (pinfunction "1_P$1") (pintype "passive"))
    )
    (net (code "58") (name "Net-(R10-1)") (class "Default")
      (node (ref "C6") (pin "1") (pinfunction "1_1") (pintype "passive"))
      (node (ref "R10") (pin "P$1") (pinfunction "1_P$1") (pintype "passive"))
    )
    (net (code "59") (name "Net-(R14-2)") (class "Default")
      (node (ref "C21") (pin "1") (pinfunction "1_1") (pintype "passive"))
      (node (ref "J5") (pin "1") (pinfunction "1_1") (pintype "passive"))
      (node (ref "R14") (pin "P$2") (pinfunction "2_P$2") (pintype "passive"))
    )
    (net (code "60") (name "Net-(R21-Pad2)") (class "Default")
      (node (ref "R21") (pin "2") (pinfunction "2_2") (pintype "passive"))
      (node (ref "TR3") (pin "3") (pinfunction "3_3") (pintype "passive"))
    )
    (net (code "61") (name "Net-(TR2-P1.2)") (class "Default")
      (node (ref "TR2") (pin "2") (pinfunction "P1.2_2") (pintype "passive"))
      (node (ref "TR2") (pin "3") (pinfunction "P2.1_3") (pintype "passive"))
    )
    (net (code "62") (name "Net-(TR2-S1.1)") (class "Default")
      (node (ref "BR2") (pin "AC1") (pinfunction "AC1_AC1") (pintype "passive"))
      (node (ref "TR2") (pin "5") (pinfunction "S1.1_5") (pintype "passive"))
      (node (ref "TR2") (pin "7") (pinfunction "S2.1_7") (pintype "passive"))
    )
    (net (code "63") (name "Net-(TR2-S1.2)") (class "Default")
      (node (ref "BR2") (pin "AC2") (pinfunction "AC2_AC2") (pintype "passive"))
      (node (ref "TR2") (pin "6") (pinfunction "S1.2_6") (pintype "passive"))
      (node (ref "TR2") (pin "8") (pinfunction "S2.2_8") (pintype "passive"))
    )
    (net (code "64") (name "Net-(TR3-Pad2)") (class "Default")
      (node (ref "TR3") (pin "2") (pinfunction "2_2") (pintype "passive"))
      (node (ref "X1") (pin "1") (pinfunction "1_1") (pintype "bidirectional"))
    )
    (net (code "65") (name "unconnected-(JP4-Pad5)") (class "Default")
      (node (ref "JP4") (pin "5") (pinfunction "5_5") (pintype "passive"))
    )
    (net (code "66") (name "unconnected-(JP4-Pad6)") (class "Default")
      (node (ref "JP4") (pin "6") (pinfunction "6_6") (pintype "passive"))
    )
    (net (code "67") (name "unconnected-(U$2-0(RX0)-Pad0)") (class "Default")
      (node (ref "U$2") (pin "0") (pinfunction "0(RX0)_0") (pintype "bidirectional"))
    )
    (net (code "68") (name "unconnected-(U$2-1(TX0)-Pad1)") (class "Default")
      (node (ref "U$2") (pin "1") (pinfunction "1(TX0)_1") (pintype "bidirectional"))
    )
    (net (code "69") (name "unconnected-(U$2-5V-Pad5V@0)") (class "Default")
      (node (ref "U$2") (pin "5V@0") (pinfunction "5V_5V@0") (pintype "bidirectional"))
    )
    (net (code "70") (name "unconnected-(U$2-14(TX3)-Pad14)") (class "Default")
      (node (ref "U$2") (pin "14") (pinfunction "14(TX3)_14") (pintype "bidirectional"))
    )
    (net (code "71") (name "unconnected-(U$2-15(RX3)-Pad15)") (class "Default")
      (node (ref "U$2") (pin "15") (pinfunction "15(RX3)_15") (pintype "bidirectional"))
    )
    (net (code "72") (name "unconnected-(U$2-16(TX2)-Pad16)") (class "Default")
      (node (ref "U$2") (pin "16") (pinfunction "16(TX2)_16") (pintype "bidirectional"))
    )
    (net (code "73") (name "unconnected-(U$2-17(RX2)-Pad17)") (class "Default")
      (node (ref "U$2") (pin "17") (pinfunction "17(RX2)_17") (pintype "bidirectional"))
    )
    (net (code "74") (name "unconnected-(U$2-18(TX1)-Pad18)") (class "Default")
      (node (ref "U$2") (pin "18") (pinfunction "18(TX1)_18") (pintype "bidirectional"))
    )
    (net (code "75") (name "unconnected-(U$2-19(RX1)-Pad19)") (class "Default")
      (node (ref "U$2") (pin "19") (pinfunction "19(RX1)_19") (pintype "bidirectional"))
    )
    (net (code "76") (name "unconnected-(U$2-20(SDA)-Pad20)") (class "Default")
      (node (ref "U$2") (pin "20") (pinfunction "20(SDA)_20") (pintype "bidirectional"))
    )
    (net (code "77") (name "unconnected-(U$2-21(SCL)-Pad21)") (class "Default")
      (node (ref "U$2") (pin "21") (pinfunction "21(SCL)_21") (pintype "bidirectional"))
    )
    (net (code "78") (name "unconnected-(U$2-A0(RX0)-PadA0)") (class "Default")
      (node (ref "U$2") (pin "A0") (pinfunction "A0(RX0)_A0") (pintype "bidirectional"))
    )
    (net (code "79") (name "unconnected-(U$2-A1(TX0)-PadA1)") (class "Default")
      (node (ref "U$2") (pin "A1") (pinfunction "A1(TX0)_A1") (pintype "bidirectional"))
    )
    (net (code "80") (name "unconnected-(U$2-GND-PadGND@1)") (class "Default")
      (node (ref "U$2") (pin "GND@1") (pinfunction "GND_GND@1") (pintype "bidirectional"))
    )
    (net (code "81") (name "unconnected-(U$2-GND-PadGND@4)") (class "Default")
      (node (ref "U$2") (pin "GND@4") (pinfunction "GND_GND@4") (pintype "bidirectional"))
    )
    (net (code "82") (name "unconnected-(U$2-Pad2)") (class "Default")
      (node (ref "U$2") (pin "2") (pinfunction "2_2") (pintype "bidirectional"))
    )
    (net (code "83") (name "unconnected-(U$2-Pad3.3V)") (class "Default")
      (node (ref "U$2") (pin "3.3V") (pinfunction "3.3V_3.3V") (pintype "bidirectional"))
    )
    (net (code "84") (name "unconnected-(U$2-Pad11)") (class "Default")
      (node (ref "U$2") (pin "11") (pinfunction "11_11") (pintype "bidirectional"))
    )
    (net (code "85") (name "unconnected-(U$2-Pad12)") (class "Default")
      (node (ref "U$2") (pin "12") (pinfunction "12_12") (pintype "bidirectional"))
    )
    (net (code "86") (name "unconnected-(U$2-Pad13)") (class "Default")
      (node (ref "U$2") (pin "13") (pinfunction "13_13") (pintype "bidirectional"))
    )
    (net (code "87") (name "unconnected-(U$2-PadA14)") (class "Default")
      (node (ref "U$2") (pin "A14") (pinfunction "A14_A14") (pintype "bidirectional"))
    )
    (net (code "88") (name "unconnected-(U$2-PadA15)") (class "Default")
      (node (ref "U$2") (pin "A15") (pinfunction "A15_A15") (pintype "bidirectional"))
    )
    (net (code "89") (name "unconnected-(U$2-PadAREF)") (class "Default")
      (node (ref "U$2") (pin "AREF") (pinfunction "AREF_AREF") (pintype "bidirectional"))
    )
    (net (code "90") (name "unconnected-(U$2-PadRESET)") (class "Default")
      (node (ref "U$2") (pin "RESET") (pinfunction "RESET_RESET") (pintype "bidirectional"))
    )
  )
)
